# schema.net
KiCad netlist of a schematic drawn in EAGLE
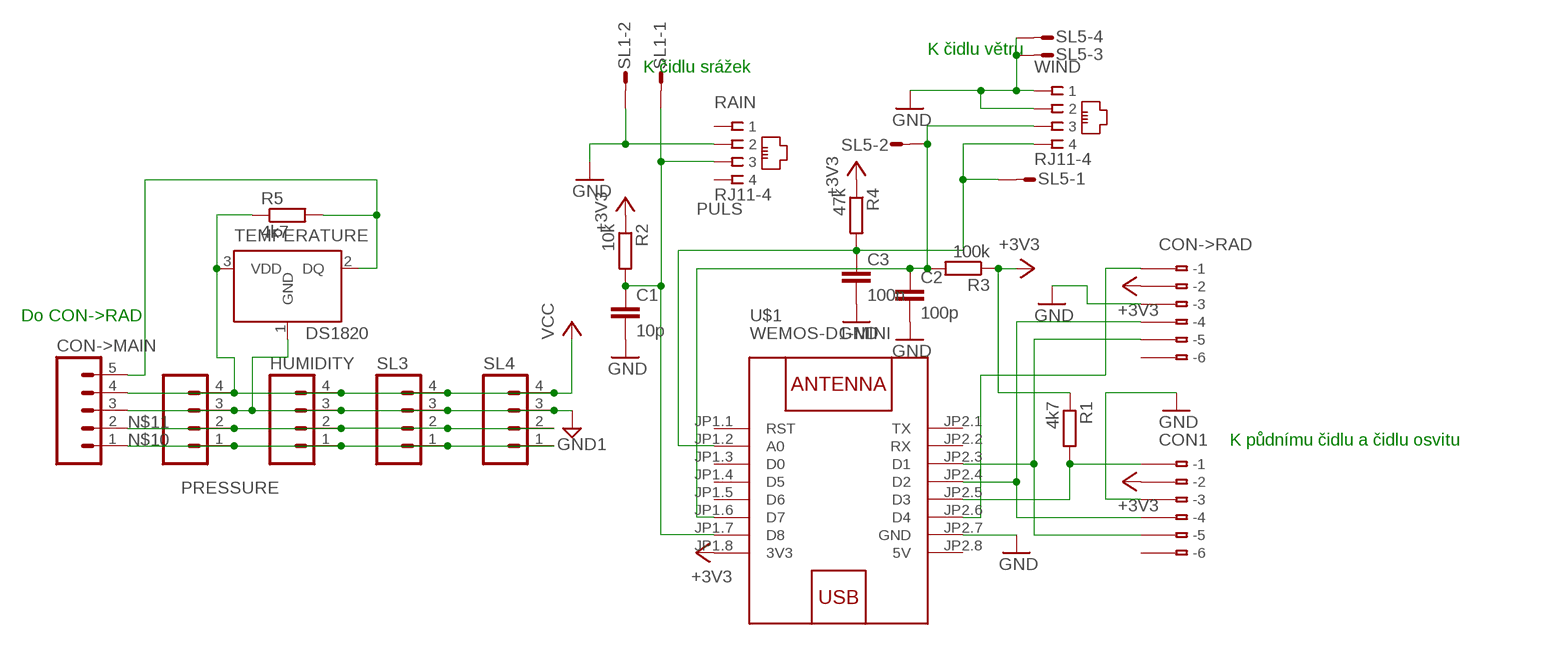
[diagram p0: schematic, sheet 1]

(export (version "E")
  (design (tool "Eeschema 10.0.6"))
  (components
    (comp (ref "C1")
      (value "10p")
      (footprint "eagle-import:C025-024X044")
      (libsource (lib "eagle-import") (part "C-EU025-024X044"))
    )
    (comp (ref "C2")
      (value "100p")
      (footprint "eagle-import:C025-024X044")
      (libsource (lib "eagle-import") (part "C-EU025-024X044"))
    )
    (comp (ref "C3")
      (value "100n")
      (footprint "eagle-import:C025-024X044")
      (libsource (lib "eagle-import") (part "C-EU025-024X044"))
    )
    (comp (ref "CON->MAIN")
      (value "M05")
      (footprint "eagle-import:05P")
      (libsource (lib "eagle-import") (part "M05"))
    )
    (comp (ref "CON->RAD")
      (value "233-506")
      (footprint "eagle-import:233-506")
      (fields (field (name "MF") "Wago Corporation") (field (name "MPN") "0233-0506"))
      (libsource (lib "eagle-import") (part "233-506"))
    )
    (comp (ref "CON1")
      (value "233-506")
      (footprint "eagle-import:233-506")
      (fields (field (name "MF") "Wago Corporation") (field (name "MPN") "0233-0506"))
      (libsource (lib "eagle-import") (part "233-506"))
    )
    (comp (ref "HUMIDITY")
      (value "M04")
      (footprint "eagle-import:04P")
      (libsource (lib "eagle-import") (part "M04"))
    )
    (comp (ref "PRESSURE")
      (value "M04")
      (footprint "eagle-import:04P")
      (libsource (lib "eagle-import") (part "M04"))
    )
    (comp (ref "R1")
      (value "4k7")
      (footprint "eagle-import:0204_7")
      (libsource (lib "eagle-import") (part "R-EU_0204/7"))
    )
    (comp (ref "R2")
      (value "10k")
      (footprint "eagle-import:0204_7")
      (libsource (lib "eagle-import") (part "R-EU_0204/7"))
    )
    (comp (ref "R3")
      (value "100k")
      (footprint "eagle-import:0204_7")
      (libsource (lib "eagle-import") (part "R-EU_0204/7"))
    )
    (comp (ref "R4")
      (value "47k")
      (footprint "eagle-import:0204_7")
      (libsource (lib "eagle-import") (part "R-EU_0204/7"))
    )
    (comp (ref "R5")
      (value "4k7")
      (footprint "eagle-import:0204_7")
      (libsource (lib "eagle-import") (part "R-EU_0204/7"))
    )
    (comp (ref "RAIN")
      (value "RJ11-4")
      (footprint "eagle-import:RJ11-4")
      (libsource (lib "eagle-import") (part "RJ11-4"))
    )
    (comp (ref "SL1")
      (value "M02S")
      (footprint "eagle-import:02P")
      (libsource (lib "eagle-import") (part "M02S"))
    )
    (comp (ref "SL3")
      (value "M04")
      (footprint "eagle-import:04P")
      (libsource (lib "eagle-import") (part "M04"))
    )
    (comp (ref "SL4")
      (value "M04")
      (footprint "eagle-import:04P")
      (libsource (lib "eagle-import") (part "M04"))
    )
    (comp (ref "SL5")
      (value "M04S")
      (footprint "eagle-import:04P")
      (libsource (lib "eagle-import") (part "M04S"))
    )
    (comp (ref "TEMPERATURE")
      (value "DS1820")
      (footprint "eagle-import:TO-92")
      (libsource (lib "eagle-import") (part "DS1820"))
    )
    (comp (ref "U$1")
      (value "WEMOS-D1-MINI")
      (footprint "eagle-import:WEMOS-D1-MINI")
      (libsource (lib "eagle-import") (part "WEMOS-D1-MINI"))
    )
    (comp (ref "WIND")
      (value "RJ11-4")
      (footprint "eagle-import:RJ11-4")
      (libsource (lib "eagle-import") (part "RJ11-4"))
    )
  )
  (nets
    (net (code "1") (name "+3V3") (class "Default")
      (node (ref "CON->RAD") (pin "B2") (pinfunction "B-2_B2") (pintype "passive"))
      (node (ref "CON1") (pin "B2") (pinfunction "B-2_B2") (pintype "passive"))
      (node (ref "R1") (pin "1") (pinfunction "1_1") (pintype "passive"))
      (node (ref "R2") (pin "1") (pinfunction "1_1") (pintype "passive"))
      (node (ref "R3") (pin "1") (pinfunction "1_1") (pintype "passive"))
      (node (ref "R4") (pin "1") (pinfunction "1_1") (pintype "passive"))
      (node (ref "U$1") (pin "JP1.8") (pinfunction "3V3_JP1.8") (pintype "power_in"))
    )
    (net (code "2") (name "/5V") (class "Default")
      (node (ref "U$1") (pin "JP2.8") (pinfunction "5V_JP2.8") (pintype "power_in"))
    )
    (net (code "3") (name "/N$10") (class "Default")
      (node (ref "CON->MAIN") (pin "1") (pinfunction "1_1") (pintype "passive"))
      (node (ref "HUMIDITY") (pin "1") (pinfunction "1_1") (pintype "passive"))
      (node (ref "PRESSURE") (pin "1") (pinfunction "1_1") (pintype "passive"))
      (node (ref "SL3") (pin "1") (pinfunction "1_1") (pintype "passive"))
      (node (ref "SL4") (pin "1") (pinfunction "1_1") (pintype "passive"))
    )
    (net (code "4") (name "/N$11") (class "Default")
      (node (ref "CON->MAIN") (pin "2") (pinfunction "2_2") (pintype "passive"))
      (node (ref "HUMIDITY") (pin "2") (pinfunction "2_2") (pintype "passive"))
      (node (ref "PRESSURE") (pin "2") (pinfunction "2_2") (pintype "passive"))
      (node (ref "SL3") (pin "2") (pinfunction "2_2") (pintype "passive"))
      (node (ref "SL4") (pin "2") (pinfunction "2_2") (pintype "passive"))
    )
    (net (code "5") (name "/PULS") (class "Default")
      (node (ref "C1") (pin "1") (pinfunction "1_1") (pintype "passive"))
      (node (ref "R2") (pin "2") (pinfunction "2_2") (pintype "passive"))
      (node (ref "RAIN") (pin "3") (pinfunction "3_3") (pintype "passive"))
      (node (ref "SL1") (pin "1") (pinfunction "S_1") (pintype "passive"))
      (node (ref "U$1") (pin "JP1.7") (pinfunction "D8_JP1.7") (pintype "bidirectional"))
    )
    (net (code "6") (name "GND") (class "Default")
      (node (ref "C1") (pin "2") (pinfunction "2_2") (pintype "passive"))
      (node (ref "C2") (pin "2") (pinfunction "2_2") (pintype "passive"))
      (node (ref "C3") (pin "2") (pinfunction "2_2") (pintype "passive"))
      (node (ref "CON->RAD") (pin "B3") (pinfunction "B-3_B3") (pintype "passive"))
      (node (ref "CON1") (pin "B3") (pinfunction "B-3_B3") (pintype "passive"))
      (node (ref "RAIN") (pin "2") (pinfunction "2_2") (pintype "passive"))
      (node (ref "SL1") (pin "2") (pinfunction "S_2") (pintype "passive"))
      (node (ref "SL5") (pin "3") (pinfunction "S_3") (pintype "passive"))
      (node (ref "SL5") (pin "4") (pinfunction "S_4") (pintype "passive"))
      (node (ref "U$1") (pin "JP2.7") (pinfunction "GND_JP2.7") (pintype "power_in"))
      (node (ref "WIND") (pin "1") (pinfunction "1_1") (pintype "passive"))
      (node (ref "WIND") (pin "2") (pinfunction "2_2") (pintype "passive"))
    )
    (net (code "7") (name "GND1") (class "Default")
      (node (ref "CON->MAIN") (pin "3") (pinfunction "3_3") (pintype "passive"))
      (node (ref "HUMIDITY") (pin "3") (pinfunction "3_3") (pintype "passive"))
      (node (ref "PRESSURE") (pin "3") (pinfunction "3_3") (pintype "passive"))
      (node (ref "SL3") (pin "3") (pinfunction "3_3") (pintype "passive"))
      (node (ref "SL4") (pin "3") (pinfunction "3_3") (pintype "passive"))
      (node (ref "TEMPERATURE") (pin "1") (pinfunction "GND_1") (pintype "power_in"))
    )
    (net (code "8") (name "Net-(CON->RAD-B-1)") (class "Default")
      (node (ref "CON->RAD") (pin "B1") (pinfunction "B-1_B1") (pintype "passive"))
      (node (ref "U$1") (pin "JP2.6") (pinfunction "D4_JP2.6") (pintype "bidirectional"))
    )
    (net (code "9") (name "Net-(CON->RAD-B-4)") (class "Default")
      (node (ref "CON->RAD") (pin "B4") (pinfunction "B-4_B4") (pintype "passive"))
      (node (ref "CON1") (pin "B4") (pinfunction "B-4_B4") (pintype "passive"))
      (node (ref "U$1") (pin "JP2.4") (pinfunction "D2_JP2.4") (pintype "bidirectional"))
    )
    (net (code "10") (name "Net-(CON->RAD-B-5)") (class "Default")
      (node (ref "CON->RAD") (pin "B5") (pinfunction "B-5_B5") (pintype "passive"))
      (node (ref "CON1") (pin "B5") (pinfunction "B-5_B5") (pintype "passive"))
      (node (ref "U$1") (pin "JP2.3") (pinfunction "D1_JP2.3") (pintype "bidirectional"))
    )
    (net (code "11") (name "Net-(CON1-B-1)") (class "Default")
      (node (ref "CON1") (pin "B1") (pinfunction "B-1_B1") (pintype "passive"))
      (node (ref "R1") (pin "2") (pinfunction "2_2") (pintype "passive"))
      (node (ref "U$1") (pin "JP2.5") (pinfunction "D3_JP2.5") (pintype "bidirectional"))
    )
    (net (code "12") (name "Net-(SL5A-S)") (class "Default")
      (node (ref "C3") (pin "1") (pinfunction "1_1") (pintype "passive"))
      (node (ref "R4") (pin "2") (pinfunction "2_2") (pintype "passive"))
      (node (ref "SL5") (pin "1") (pinfunction "S_1") (pintype "passive"))
      (node (ref "U$1") (pin "JP1.2") (pinfunction "A0_JP1.2") (pintype "bidirectional"))
      (node (ref "WIND") (pin "4") (pinfunction "4_4") (pintype "passive"))
    )
    (net (code "13") (name "Net-(SL5B-S)") (class "Default")
      (node (ref "C2") (pin "1") (pinfunction "1_1") (pintype "passive"))
      (node (ref "R3") (pin "2") (pinfunction "2_2") (pintype "passive"))
      (node (ref "SL5") (pin "2") (pinfunction "S_2") (pintype "passive"))
      (node (ref "U$1") (pin "JP1.6") (pinfunction "D7_JP1.6") (pintype "bidirectional"))
      (node (ref "WIND") (pin "3") (pinfunction "3_3") (pintype "passive"))
    )
    (net (code "14") (name "Net-(TEMPERATURE-DQ)") (class "Default")
      (node (ref "CON->MAIN") (pin "5") (pinfunction "5_5") (pintype "passive"))
      (node (ref "R5") (pin "2") (pinfunction "2_2") (pintype "passive"))
      (node (ref "TEMPERATURE") (pin "2") (pinfunction "DQ_2") (pintype "output"))
    )
    (net (code "15") (name "VCC") (class "Default")
      (node (ref "CON->MAIN") (pin "4") (pinfunction "4_4") (pintype "passive"))
      (node (ref "HUMIDITY") (pin "4") (pinfunction "4_4") (pintype "passive"))
      (node (ref "PRESSURE") (pin "4") (pinfunction "4_4") (pintype "passive"))
      (node (ref "R5") (pin "1") (pinfunction "1_1") (pintype "passive"))
      (node (ref "SL3") (pin "4") (pinfunction "4_4") (pintype "passive"))
      (node (ref "SL4") (pin "4") (pinfunction "4_4") (pintype "passive"))
      (node (ref "TEMPERATURE") (pin "3") (pinfunction "VDD_3") (pintype "input"))
    )
    (net (code "16") (name "unconnected-(CON->RAD--1-PadA1)") (class "Default")
      (node (ref "CON->RAD") (pin "A1") (pinfunction "-1_A1") (pintype "passive"))
    )
    (net (code "17") (name "unconnected-(CON->RAD--2-PadA2)") (class "Default")
      (node (ref "CON->RAD") (pin "A2") (pinfunction "-2_A2") (pintype "passive"))
    )
    (net (code "18") (name "unconnected-(CON->RAD--3-PadA3)") (class "Default")
      (node (ref "CON->RAD") (pin "A3") (pinfunction "-3_A3") (pintype "passive"))
    )
    (net (code "19") (name "unconnected-(CON->RAD--4-PadA4)") (class "Default")
      (node (ref "CON->RAD") (pin "A4") (pinfunction "-4_A4") (pintype "passive"))
    )
    (net (code "20") (name "unconnected-(CON->RAD--5-PadA5)") (class "Default")
      (node (ref "CON->RAD") (pin "A5") (pinfunction "-5_A5") (pintype "passive"))
    )
    (net (code "21") (name "unconnected-(CON->RAD--6-PadA6)") (class "Default")
      (node (ref "CON->RAD") (pin "A6") (pinfunction "-6_A6") (pintype "passive"))
    )
    (net (code "22") (name "unconnected-(CON->RAD-B-6-PadB6)") (class "Default")
      (node (ref "CON->RAD") (pin "B6") (pinfunction "B-6_B6") (pintype "passive"))
    )
    (net (code "23") (name "unconnected-(CON1--1-PadA1)") (class "Default")
      (node (ref "CON1") (pin "A1") (pinfunction "-1_A1") (pintype "passive"))
    )
    (net (code "24") (name "unconnected-(CON1--2-PadA2)") (class "Default")
      (node (ref "CON1") (pin "A2") (pinfunction "-2_A2") (pintype "passive"))
    )
    (net (code "25") (name "unconnected-(CON1--3-PadA3)") (class "Default")
      (node (ref "CON1") (pin "A3") (pinfunction "-3_A3") (pintype "passive"))
    )
    (net (code "26") (name "unconnected-(CON1--4-PadA4)") (class "Default")
      (node (ref "CON1") (pin "A4") (pinfunction "-4_A4") (pintype "passive"))
    )
    (net (code "27") (name "unconnected-(CON1--5-PadA5)") (class "Default")
      (node (ref "CON1") (pin "A5") (pinfunction "-5_A5") (pintype "passive"))
    )
    (net (code "28") (name "unconnected-(CON1--6-PadA6)") (class "Default")
      (node (ref "CON1") (pin "A6") (pinfunction "-6_A6") (pintype "passive"))
    )
    (net (code "29") (name "unconnected-(CON1-B-6-PadB6)") (class "Default")
      (node (ref "CON1") (pin "B6") (pinfunction "B-6_B6") (pintype "passive"))
    )
    (net (code "30") (name "unconnected-(RAIN-Pad1)") (class "Default")
      (node (ref "RAIN") (pin "1") (pinfunction "1_1") (pintype "passive"))
    )
    (net (code "31") (name "unconnected-(RAIN-Pad4)") (class "Default")
      (node (ref "RAIN") (pin "4") (pinfunction "4_4") (pintype "passive"))
    )
    (net (code "32") (name "unconnected-(U$1-D0-PadJP1.3)") (class "Default")
      (node (ref "U$1") (pin "JP1.3") (pinfunction "D0_JP1.3") (pintype "bidirectional"))
    )
    (net (code "33") (name "unconnected-(U$1-D5-PadJP1.4)") (class "Default")
      (node (ref "U$1") (pin "JP1.4") (pinfunction "D5_JP1.4") (pintype "bidirectional"))
    )
    (net (code "34") (name "unconnected-(U$1-D6-PadJP1.5)") (class "Default")
      (node (ref "U$1") (pin "JP1.5") (pinfunction "D6_JP1.5") (pintype "bidirectional"))
    )
    (net (code "35") (name "unconnected-(U$1-RST-PadJP1.1)") (class "Default")
      (node (ref "U$1") (pin "JP1.1") (pinfunction "RST_JP1.1") (pintype "bidirectional"))
    )
    (net (code "36") (name "unconnected-(U$1-RX-PadJP2.2)") (class "Default")
      (node (ref "U$1") (pin "JP2.2") (pinfunction "RX_JP2.2") (pintype "bidirectional"))
    )
    (net (code "37") (name "unconnected-(U$1-TX-PadJP2.1)") (class "Default")
      (node (ref "U$1") (pin "JP2.1") (pinfunction "TX_JP2.1") (pintype "bidirectional"))
    )
  )
)
